# Clock.net
KiCad netlist of a schematic drawn in Altium Designer
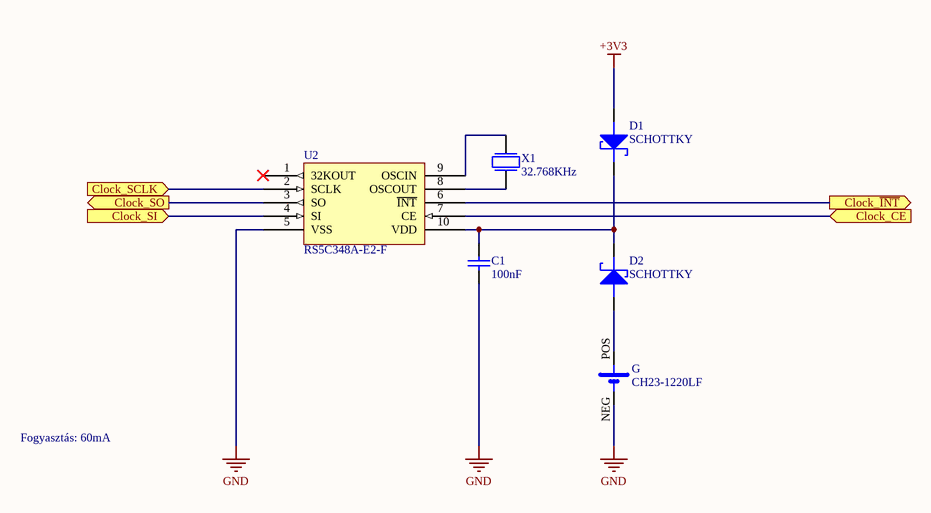
[diagram p0: Clock.SchDoc]

(export (version "E")
  (design (tool "Eeschema 10.0.6"))
  (components
    (comp (ref "C1")
      (value "100nF")
      (footprint "FP_0805_CAP_085")
      (description "Capacitor")
      (fields (field (name "TOLERANCE") "10%") (field (name "VOLTAGE") "50V"))
      (libsource (lib "hallglib") (part "CAP"))
    )
    (comp (ref "D1")
      (value "SCHOTTKY")
      (footprint "FP_SOD323-F")
      (description "Schottky diode")
      (libsource (lib "hallglib") (part "SCHOTTKY"))
    )
    (comp (ref "D2")
      (value "SCHOTTKY")
      (footprint "FP_SOD323-F")
      (description "Schottky diode")
      (libsource (lib "hallglib") (part "SCHOTTKY"))
    )
    (comp (ref "G")
      (value "CH23-1220LF")
      (footprint "CH23-1220LF")
      (fields (field (name "MF") "Multicomp"))
      (libsource (lib "CH23-1220LF") (part "CH23-1220LF"))
    )
    (comp (ref "U2")
      (value "RS5C348A-E2-F")
      (footprint "TSSOP50P640X135-10M")
      (description "Real-time clock")
      (libsource (lib "hallglib") (part "RS5C348A-E2-F"))
    )
    (comp (ref "X1")
      (value "32.768KHz")
      (footprint "NXG 2x6 footprint")
      (description "Quarz Crystal")
      (libsource (lib "hallglib") (part "Crystal"))
    )
  )
  (nets
    (net (code "1") (name "+3V3") (class "Default")
      (node (ref "D1") (pin "1") (pinfunction "ANODE_1") (pintype "passive"))
    )
    (net (code "2") (name "/Clock_CE") (class "Default")
      (node (ref "U2") (pin "7") (pinfunction "CE_7") (pintype "input"))
    )
    (net (code "3") (name "/Clock_SCLK") (class "Default")
      (node (ref "U2") (pin "2") (pinfunction "SCLK_2") (pintype "input"))
    )
    (net (code "4") (name "/Clock_SI") (class "Default")
      (node (ref "U2") (pin "4") (pinfunction "SI_4") (pintype "input"))
    )
    (net (code "5") (name "/Clock_SO") (class "Default")
      (node (ref "U2") (pin "3") (pinfunction "SO_3") (pintype "output"))
    )
    (net (code "6") (name "/Clock_~{INT}") (class "Default")
      (node (ref "U2") (pin "6") (pinfunction "~{INT}_6") (pintype "open_collector"))
    )
    (net (code "7") (name "GND") (class "Default")
      (node (ref "C1") (pin "1") (pinfunction "1_1") (pintype "passive"))
      (node (ref "G") (pin "NEG") (pinfunction "NEG_NEG") (pintype "passive"))
      (node (ref "U2") (pin "5") (pinfunction "VSS_5") (pintype "power_in"))
    )
    (net (code "8") (name "Net-(D1-CATHODE)") (class "Default")
      (node (ref "C1") (pin "2") (pinfunction "2_2") (pintype "passive"))
      (node (ref "D1") (pin "2") (pinfunction "CATHODE_2") (pintype "passive"))
      (node (ref "D2") (pin "2") (pinfunction "CATHODE_2") (pintype "passive"))
      (node (ref "U2") (pin "10") (pinfunction "VDD_10") (pintype "power_in"))
    )
    (net (code "9") (name "Net-(D2-ANODE)") (class "Default")
      (node (ref "D2") (pin "1") (pinfunction "ANODE_1") (pintype "passive"))
      (node (ref "G") (pin "POS") (pinfunction "POS_POS") (pintype "passive"))
    )
    (net (code "10") (name "Net-(U2-OSCIN)") (class "Default")
      (node (ref "U2") (pin "9") (pinfunction "OSCIN_9") (pintype "passive"))
      (node (ref "X1") (pin "1") (pinfunction "1_1") (pintype "passive"))
    )
    (net (code "11") (name "Net-(U2-OSCOUT)") (class "Default")
      (node (ref "U2") (pin "8") (pinfunction "OSCOUT_8") (pintype "passive"))
      (node (ref "X1") (pin "2") (pinfunction "2_2") (pintype "passive"))
    )
    (net (code "12") (name "unconnected-(U2-32KOUT-Pad1)") (class "Default")
      (node (ref "U2") (pin "1") (pinfunction "32KOUT_1") (pintype "output+no_connect"))
    )
  )
)
